# WCH-Link-R1.net
KiCad netlist of a schematic drawn in Altium Designer
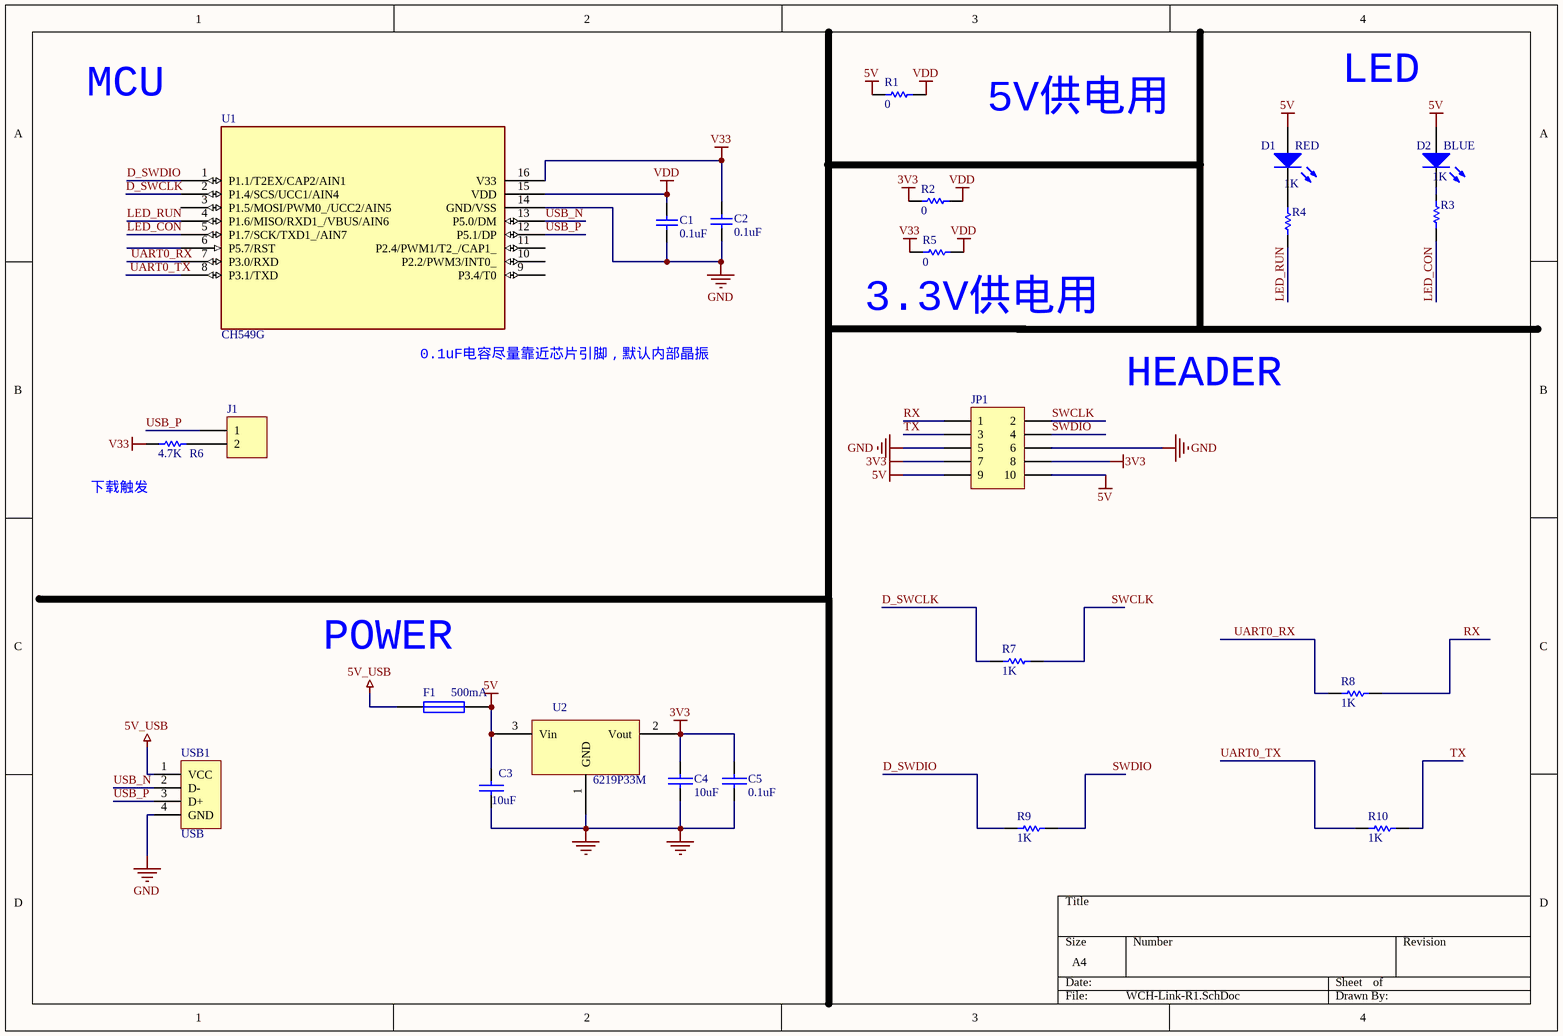
[diagram p0: WCH-Link-R1.SchDoc]

(export (version "E")
  (design (tool "Eeschema 10.0.6"))
  (components
    (comp (ref "C1")
      (value "0.1uF")
      (footprint "0603_C")
      (description "Capacitor")
      (fields (field (name "PUBLISHER") "Altium Limited"))
      (libsource (lib "MYLIB") (part "C-RAD-0603"))
    )
    (comp (ref "C2")
      (value "0.1uF")
      (footprint "0603_C")
      (description "Capacitor")
      (fields (field (name "PUBLISHER") "Altium Limited"))
      (libsource (lib "MYLIB") (part "C-RAD-0603"))
    )
    (comp (ref "C3")
      (value "10uF")
      (footprint "3216_C")
      (description "Capacitor")
      (libsource (lib "*") (part "CAP"))
    )
    (comp (ref "C4")
      (value "10uF")
      (footprint "3216_C")
      (description "Capacitor")
      (libsource (lib "*") (part "CAP"))
    )
    (comp (ref "C5")
      (value "0.1uF")
      (footprint "0603_C")
      (description "Capacitor")
      (libsource (lib "*") (part "CAP"))
    )
    (comp (ref "D1")
      (value "RED")
      (footprint "0603+")
      (description "Typical RED, GREEN, YELLOW, AMBER GaAs LED")
      (fields (field (name "PUBLISHER") "Altium Limited"))
      (libsource (lib "MYLIB") (part "D0603"))
    )
    (comp (ref "D2")
      (value "BLUE")
      (footprint "0603+")
      (description "Typical RED, GREEN, YELLOW, AMBER GaAs LED")
      (fields (field (name "PUBLISHER") "Altium Limited"))
      (libsource (lib "MYLIB") (part "D0603"))
    )
    (comp (ref "F1")
      (value "500mA")
      (footprint "0805")
      (description "Fuse")
      (libsource (lib "*") (part "FUSE1"))
    )
    (comp (ref "J1")
      (value "Header 2")
      (footprint "SIP2-2.54MM")
      (description "Header, 2-Pin")
      (fields (field (name "PUBLISHER") "Altium Limited"))
      (libsource (lib "Miscellaneous Connectors") (part "Header 2"))
    )
    (comp (ref "JP1")
      (value "Header 5*2")
      (footprint "IDCS10-2.54mm")
      (description "Header, 10Pin")
      (fields (field (name "PUBLISHER") "Altium Limited"))
      (libsource (lib "WCH-DAPLINK-R0-1v2") (part "Header_5*2"))
    )
    (comp (ref "R1")
      (value "0")
      (footprint "0603")
      (description "Resistor")
      (fields (field (name "PUBLISHER") "Altium Limited"))
      (libsource (lib "MYLIB") (part "0603-1"))
    )
    (comp (ref "R2")
      (value "0")
      (footprint "0603")
      (description "Resistor")
      (fields (field (name "PUBLISHER") "Altium Limited"))
      (libsource (lib "MYLIB") (part "0603-1"))
    )
    (comp (ref "R3")
      (value "1K")
      (footprint "0603")
      (description "Resistor")
      (fields (field (name "PUBLISHER") "Altium Limited"))
      (libsource (lib "MYLIB") (part "0603-1"))
    )
    (comp (ref "R4")
      (value "1K")
      (footprint "0603")
      (description "Resistor")
      (fields (field (name "PUBLISHER") "Altium Limited"))
      (libsource (lib "MYLIB") (part "0603-1"))
    )
    (comp (ref "R5")
      (value "0")
      (footprint "0603")
      (description "Resistor")
      (fields (field (name "PUBLISHER") "Altium Limited"))
      (libsource (lib "MYLIB") (part "0603-1"))
    )
    (comp (ref "R6")
      (value "4.7K")
      (footprint "0603")
      (description "Resistor")
      (fields (field (name "PUBLISHER") "Altium Limited"))
      (libsource (lib "MYLIB") (part "0603-1"))
    )
    (comp (ref "R7")
      (value "1K")
      (footprint "0603")
      (description "Resistor")
      (fields (field (name "PUBLISHER") "Altium Limited"))
      (libsource (lib "MYLIB") (part "0603-1"))
    )
    (comp (ref "R8")
      (value "1K")
      (footprint "0603")
      (description "Resistor")
      (fields (field (name "PUBLISHER") "Altium Limited"))
      (libsource (lib "MYLIB") (part "0603-1"))
    )
    (comp (ref "R9")
      (value "1K")
      (footprint "0603")
      (description "Resistor")
      (fields (field (name "PUBLISHER") "Altium Limited"))
      (libsource (lib "MYLIB") (part "0603-1"))
    )
    (comp (ref "R10")
      (value "1K")
      (footprint "CHXXXPCB:0603")
      (description "Resistor")
      (fields (field (name "PUBLISHER") "Altium Limited"))
      (libsource (lib "MYLIB") (part "0603-1"))
    )
    (comp (ref "U1")
      (value "CH549G")
      (footprint "SOP16")
      (description "8bit MCS51 MCU with ADC & USB type-C host & device & dual UART & SPI")
      (libsource (lib "CHXXXSCH(1)") (part "CH549G"))
    )
    (comp (ref "U2")
      (value "6219P33M")
      (footprint "SOT-23")
      (libsource (lib "wch_sch_others") (part "6219P33M"))
    )
    (comp (ref "USB1") (value "USB") (footprint "USB-A-F/P_B") (libsource (lib "nanoDAP") (part "USB_G")))
  )
  (nets
    (net (code "1") (name "/D_SWCLK") (class "Default")
      (node (ref "R7") (pin "2") (pinfunction "2_2") (pintype "passive"))
      (node (ref "U1") (pin "2") (pinfunction "P1.4/SCS/UCC1/AIN4_2") (pintype "bidirectional"))
    )
    (net (code "2") (name "/D_SWDIO") (class "Default")
      (node (ref "R9") (pin "2") (pinfunction "2_2") (pintype "passive"))
      (node (ref "U1") (pin "1") (pinfunction "P1.1/T2EX/CAP2/AIN1_1") (pintype "bidirectional"))
    )
    (net (code "3") (name "/LED_CON") (class "Default")
      (node (ref "R3") (pin "1") (pinfunction "1_1") (pintype "passive"))
      (node (ref "U1") (pin "5") (pinfunction "P1.7/SCK/TXD1_/AIN7_5") (pintype "bidirectional"))
    )
    (net (code "4") (name "/LED_RUN") (class "Default")
      (node (ref "R4") (pin "1") (pinfunction "1_1") (pintype "passive"))
      (node (ref "U1") (pin "4") (pinfunction "P1.6/MISO/RXD1_/VBUS/AIN6_4") (pintype "bidirectional"))
    )
    (net (code "5") (name "/RX") (class "Default")
      (node (ref "JP1") (pin "1") (pinfunction "1_1") (pintype "passive"))
      (node (ref "R8") (pin "1") (pinfunction "1_1") (pintype "passive"))
    )
    (net (code "6") (name "/SWCLK") (class "Default")
      (node (ref "JP1") (pin "2") (pinfunction "2_2") (pintype "passive"))
      (node (ref "R7") (pin "1") (pinfunction "1_1") (pintype "passive"))
    )
    (net (code "7") (name "/SWDIO") (class "Default")
      (node (ref "JP1") (pin "4") (pinfunction "4_4") (pintype "passive"))
      (node (ref "R9") (pin "1") (pinfunction "1_1") (pintype "passive"))
    )
    (net (code "8") (name "/TX") (class "Default")
      (node (ref "JP1") (pin "3") (pinfunction "3_3") (pintype "passive"))
      (node (ref "R10") (pin "1") (pinfunction "1_1") (pintype "passive"))
    )
    (net (code "9") (name "/UART0_RX") (class "Default")
      (node (ref "R8") (pin "2") (pinfunction "2_2") (pintype "passive"))
      (node (ref "U1") (pin "7") (pinfunction "P3.0/RXD_7") (pintype "bidirectional"))
    )
    (net (code "10") (name "/UART0_TX") (class "Default")
      (node (ref "R10") (pin "2") (pinfunction "2_2") (pintype "passive"))
      (node (ref "U1") (pin "8") (pinfunction "P3.1/TXD_8") (pintype "bidirectional"))
    )
    (net (code "11") (name "/USB_N") (class "Default")
      (node (ref "U1") (pin "13") (pinfunction "P5.0/DM_13") (pintype "bidirectional"))
      (node (ref "USB1") (pin "2") (pinfunction "D-_2") (pintype "passive"))
    )
    (net (code "12") (name "/USB_P") (class "Default")
      (node (ref "J1") (pin "1") (pinfunction "1_1") (pintype "passive"))
      (node (ref "U1") (pin "12") (pinfunction "P5.1/DP_12") (pintype "bidirectional"))
      (node (ref "USB1") (pin "3") (pinfunction "D+_3") (pintype "passive"))
    )
    (net (code "13") (name "3V3") (class "Default")
      (node (ref "C4") (pin "1") (pinfunction "1_1") (pintype "passive"))
      (node (ref "C5") (pin "1") (pinfunction "1_1") (pintype "passive"))
      (node (ref "JP1") (pin "7") (pinfunction "7_7") (pintype "passive"))
      (node (ref "JP1") (pin "8") (pinfunction "8_8") (pintype "passive"))
      (node (ref "R2") (pin "2") (pinfunction "2_2") (pintype "passive"))
      (node (ref "U2") (pin "2") (pinfunction "Vout_2") (pintype "passive"))
    )
    (net (code "14") (name "5V") (class "Default")
      (node (ref "C3") (pin "1") (pinfunction "1_1") (pintype "passive"))
      (node (ref "D1") (pin "1") (pinfunction "A_1") (pintype "passive"))
      (node (ref "D2") (pin "1") (pinfunction "A_1") (pintype "passive"))
      (node (ref "F1") (pin "2") (pinfunction "2_2") (pintype "passive"))
      (node (ref "JP1") (pin "10") (pinfunction "10_10") (pintype "passive"))
      (node (ref "JP1") (pin "9") (pinfunction "9_9") (pintype "passive"))
      (node (ref "R1") (pin "2") (pinfunction "2_2") (pintype "passive"))
      (node (ref "U2") (pin "3") (pinfunction "Vin_3") (pintype "passive"))
    )
    (net (code "15") (name "5V_USB") (class "Default")
      (node (ref "F1") (pin "1") (pinfunction "1_1") (pintype "passive"))
      (node (ref "USB1") (pin "1") (pinfunction "VCC_1") (pintype "passive"))
    )
    (net (code "16") (name "GND") (class "Default")
      (node (ref "C1") (pin "2") (pinfunction "2_2") (pintype "passive"))
      (node (ref "C2") (pin "2") (pinfunction "2_2") (pintype "passive"))
      (node (ref "C3") (pin "2") (pinfunction "2_2") (pintype "passive"))
      (node (ref "C4") (pin "2") (pinfunction "2_2") (pintype "passive"))
      (node (ref "C5") (pin "2") (pinfunction "2_2") (pintype "passive"))
      (node (ref "JP1") (pin "5") (pinfunction "5_5") (pintype "passive"))
      (node (ref "JP1") (pin "6") (pinfunction "6_6") (pintype "passive"))
      (node (ref "U1") (pin "14") (pinfunction "GND/VSS_14") (pintype "power_in"))
      (node (ref "U2") (pin "1") (pinfunction "GND_1") (pintype "passive"))
      (node (ref "USB1") (pin "4") (pinfunction "GND_4") (pintype "passive"))
    )
    (net (code "17") (name "Net-(D1-K)") (class "Default")
      (node (ref "D1") (pin "2") (pinfunction "K_2") (pintype "passive"))
      (node (ref "R4") (pin "2") (pinfunction "2_2") (pintype "passive"))
    )
    (net (code "18") (name "Net-(D2-K)") (class "Default")
      (node (ref "D2") (pin "2") (pinfunction "K_2") (pintype "passive"))
      (node (ref "R3") (pin "2") (pinfunction "2_2") (pintype "passive"))
    )
    (net (code "19") (name "Net-(J1-Pad2)") (class "Default")
      (node (ref "J1") (pin "2") (pinfunction "2_2") (pintype "passive"))
      (node (ref "R6") (pin "1") (pinfunction "1_1") (pintype "passive"))
    )
    (net (code "20") (name "V33") (class "Default")
      (node (ref "C2") (pin "1") (pinfunction "1_1") (pintype "passive"))
      (node (ref "R5") (pin "2") (pinfunction "2_2") (pintype "passive"))
      (node (ref "R6") (pin "2") (pinfunction "2_2") (pintype "passive"))
      (node (ref "U1") (pin "16") (pinfunction "V33_16") (pintype "power_in"))
    )
    (net (code "21") (name "VDD") (class "Default")
      (node (ref "C1") (pin "1") (pinfunction "1_1") (pintype "passive"))
      (node (ref "R1") (pin "1") (pinfunction "1_1") (pintype "passive"))
      (node (ref "R2") (pin "1") (pinfunction "1_1") (pintype "passive"))
      (node (ref "R5") (pin "1") (pinfunction "1_1") (pintype "passive"))
      (node (ref "U1") (pin "15") (pinfunction "VDD_15") (pintype "power_in"))
    )
    (net (code "22") (name "unconnected-(U1-P1.5{slash}MOSI{slash}PWM0_{slash}UCC2{slash}AIN5-Pad3)") (class "Default")
      (node (ref "U1") (pin "3") (pinfunction "P1.5/MOSI/PWM0_/UCC2/AIN5_3") (pintype "bidirectional"))
    )
    (net (code "23") (name "unconnected-(U1-P2.2{slash}PWM3{slash}INT0_-Pad10)") (class "Default")
      (node (ref "U1") (pin "10") (pinfunction "P2.2/PWM3/INT0__10") (pintype "bidirectional"))
    )
    (net (code "24") (name "unconnected-(U1-P2.4{slash}PWM1{slash}T2_{slash}CAP1_-Pad11)") (class "Default")
      (node (ref "U1") (pin "11") (pinfunction "P2.4/PWM1/T2_/CAP1__11") (pintype "bidirectional"))
    )
    (net (code "25") (name "unconnected-(U1-P3.4{slash}T0-Pad9)") (class "Default")
      (node (ref "U1") (pin "9") (pinfunction "P3.4/T0_9") (pintype "bidirectional"))
    )
    (net (code "26") (name "unconnected-(U1-P5.7{slash}RST-Pad6)") (class "Default")
      (node (ref "U1") (pin "6") (pinfunction "P5.7/RST_6") (pintype "input"))
    )
  )
)
